# MAX30105.net
KiCad netlist of a schematic drawn in Altium Designer
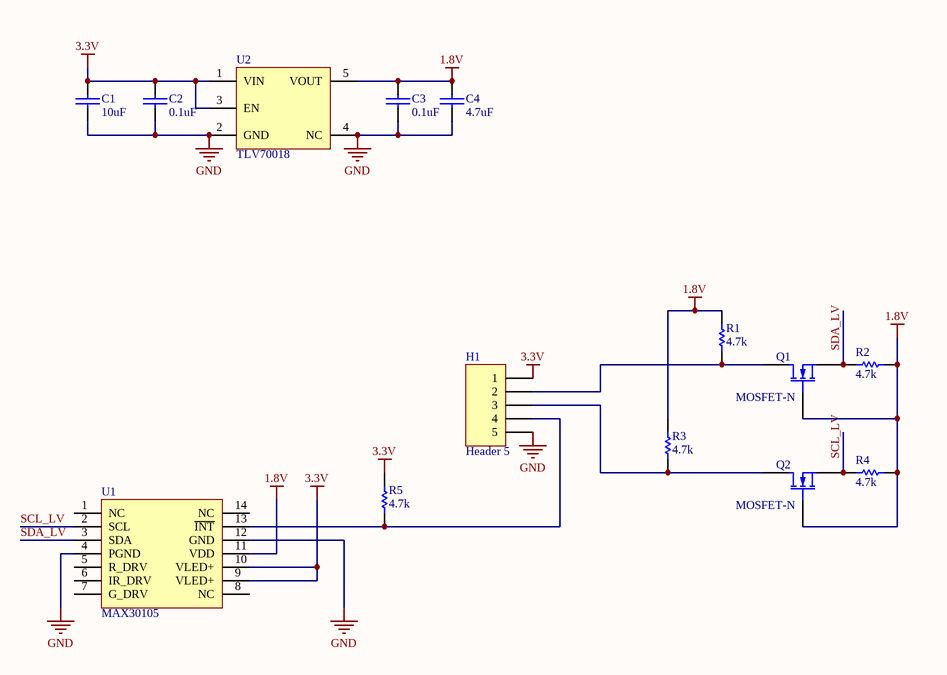
[diagram p0: MAX30105.SchDoc]

(export (version "E")
  (design (tool "Eeschema 10.0.6"))
  (components
    (comp (ref "C1")
      (value "10uF")
      (footprint "0402[IMP]")
      (fields (field (name "VOLTAGE") "CMAX"))
      (libsource (lib "Biosense_Altium_Library") (part "CAPACITOR"))
    )
    (comp (ref "C2")
      (value "0.1uF")
      (footprint "0402[IMP]")
      (fields (field (name "VOLTAGE") "CMAX"))
      (libsource (lib "Biosense_Altium_Library") (part "CAPACITOR"))
    )
    (comp (ref "C3")
      (value "0.1uF")
      (footprint "0402[IMP]")
      (fields (field (name "VOLTAGE") "CMAX"))
      (libsource (lib "Biosense_Altium_Library") (part "CAPACITOR"))
    )
    (comp (ref "C4")
      (value "4.7uF")
      (footprint "0402[IMP]")
      (fields (field (name "VOLTAGE") "CMAX"))
      (libsource (lib "Biosense_Altium_Library") (part "CAPACITOR"))
    )
    (comp (ref "H1")
      (value "Header 5")
      (footprint "I2C_Header")
      (libsource (lib "Biosense_Altium_Library") (part "Header 5"))
    )
    (comp (ref "Q1")
      (value "MOSFET-N")
      (footprint "SOT23")
      (description "N-Channel MOSFET")
      (fields (field (name "PUBLISHER") "Altium Limited"))
      (libsource (lib "Miscellaneous Devices") (part "MOSFET-N"))
    )
    (comp (ref "Q2")
      (value "MOSFET-N")
      (footprint "SOT23")
      (description "N-Channel MOSFET")
      (fields (field (name "PUBLISHER") "Altium Limited"))
      (libsource (lib "Miscellaneous Devices") (part "MOSFET-N"))
    )
    (comp (ref "R1")
      (value "4.7k")
      (footprint "0402[IMP]")
      (libsource (lib "Biosense_Altium_Library") (part "RESISTOR"))
    )
    (comp (ref "R2")
      (value "4.7k")
      (footprint "0402[IMP]")
      (libsource (lib "Biosense_Altium_Library") (part "RESISTOR"))
    )
    (comp (ref "R3")
      (value "4.7k")
      (footprint "0402[IMP]")
      (libsource (lib "Biosense_Altium_Library") (part "RESISTOR"))
    )
    (comp (ref "R4")
      (value "4.7k")
      (footprint "0402[IMP]")
      (libsource (lib "Biosense_Altium_Library") (part "RESISTOR"))
    )
    (comp (ref "R5")
      (value "4.7k")
      (footprint "0402[IMP]")
      (libsource (lib "Biosense_Altium_Library") (part "RESISTOR"))
    )
    (comp (ref "U1")
      (value "MAX30105")
      (footprint "OLGA-14")
      (libsource (lib "Biosense_Altium_Library") (part "MAX30105"))
    )
    (comp (ref "U2")
      (value "TLV70018")
      (footprint "SC70-5pin")
      (libsource (lib "Biosense_Altium_Library") (part "SP6214"))
    )
  )
  (nets
    (net (code "1") (name "/SCL_LV") (class "Default")
      (node (ref "Q2") (pin "3") (pinfunction "S_3") (pintype "passive"))
      (node (ref "R4") (pin "2") (pinfunction "2_2") (pintype "passive"))
      (node (ref "U1") (pin "2") (pinfunction "SCL_2") (pintype "passive"))
    )
    (net (code "2") (name "/SDA_LV") (class "Default")
      (node (ref "Q1") (pin "3") (pinfunction "S_3") (pintype "passive"))
      (node (ref "R2") (pin "2") (pinfunction "2_2") (pintype "passive"))
      (node (ref "U1") (pin "3") (pinfunction "SDA_3") (pintype "passive"))
    )
    (net (code "3") (name "1.8V") (class "Default")
      (node (ref "C3") (pin "1") (pinfunction "1_1") (pintype "passive"))
      (node (ref "C4") (pin "1") (pinfunction "1_1") (pintype "passive"))
      (node (ref "Q1") (pin "2") (pinfunction "G_2") (pintype "passive"))
      (node (ref "Q2") (pin "2") (pinfunction "G_2") (pintype "passive"))
      (node (ref "R1") (pin "2") (pinfunction "2_2") (pintype "passive"))
      (node (ref "R2") (pin "1") (pinfunction "1_1") (pintype "passive"))
      (node (ref "R3") (pin "2") (pinfunction "2_2") (pintype "passive"))
      (node (ref "R4") (pin "1") (pinfunction "1_1") (pintype "passive"))
      (node (ref "U1") (pin "11") (pinfunction "VDD_11") (pintype "passive"))
      (node (ref "U2") (pin "5") (pinfunction "VOUT_5") (pintype "passive"))
    )
    (net (code "4") (name "3.3V") (class "Default")
      (node (ref "C1") (pin "1") (pinfunction "1_1") (pintype "passive"))
      (node (ref "C2") (pin "1") (pinfunction "1_1") (pintype "passive"))
      (node (ref "H1") (pin "1") (pinfunction "1_1") (pintype "passive"))
      (node (ref "R5") (pin "2") (pinfunction "2_2") (pintype "passive"))
      (node (ref "U1") (pin "10") (pinfunction "VLED+_10") (pintype "passive"))
      (node (ref "U1") (pin "9") (pinfunction "VLED+_9") (pintype "passive"))
      (node (ref "U2") (pin "1") (pinfunction "VIN_1") (pintype "passive"))
      (node (ref "U2") (pin "3") (pinfunction "EN_3") (pintype "passive"))
    )
    (net (code "5") (name "GND") (class "Default")
      (node (ref "C1") (pin "2") (pinfunction "2_2") (pintype "passive"))
      (node (ref "C2") (pin "2") (pinfunction "2_2") (pintype "passive"))
      (node (ref "C3") (pin "2") (pinfunction "2_2") (pintype "passive"))
      (node (ref "C4") (pin "2") (pinfunction "2_2") (pintype "passive"))
      (node (ref "H1") (pin "5") (pinfunction "5_5") (pintype "passive"))
      (node (ref "U1") (pin "12") (pinfunction "GND_12") (pintype "passive"))
      (node (ref "U1") (pin "4") (pinfunction "PGND_4") (pintype "passive"))
      (node (ref "U2") (pin "2") (pinfunction "GND_2") (pintype "passive"))
      (node (ref "U2") (pin "4") (pinfunction "NC_4") (pintype "passive"))
    )
    (net (code "6") (name "Net-(Q1-D)") (class "Default")
      (node (ref "H1") (pin "2") (pinfunction "2_2") (pintype "passive"))
      (node (ref "Q1") (pin "1") (pinfunction "D_1") (pintype "passive"))
      (node (ref "R1") (pin "1") (pinfunction "1_1") (pintype "passive"))
    )
    (net (code "7") (name "Net-(Q2-D)") (class "Default")
      (node (ref "H1") (pin "3") (pinfunction "3_3") (pintype "passive"))
      (node (ref "Q2") (pin "1") (pinfunction "D_1") (pintype "passive"))
      (node (ref "R3") (pin "1") (pinfunction "1_1") (pintype "passive"))
    )
    (net (code "8") (name "Net-(U1-~{INT})") (class "Default")
      (node (ref "H1") (pin "4") (pinfunction "4_4") (pintype "passive"))
      (node (ref "R5") (pin "1") (pinfunction "1_1") (pintype "passive"))
      (node (ref "U1") (pin "13") (pinfunction "~{INT}_13") (pintype "passive"))
    )
    (net (code "9") (name "unconnected-(U1-G_DRV-Pad7)") (class "Default")
      (node (ref "U1") (pin "7") (pinfunction "G_DRV_7") (pintype "passive"))
    )
    (net (code "10") (name "unconnected-(U1-IR_DRV-Pad6)") (class "Default")
      (node (ref "U1") (pin "6") (pinfunction "IR_DRV_6") (pintype "passive"))
    )
    (net (code "11") (name "unconnected-(U1-NC-Pad1)") (class "Default")
      (node (ref "U1") (pin "1") (pinfunction "NC_1") (pintype "passive"))
    )
    (net (code "12") (name "unconnected-(U1-NC-Pad8)") (class "Default")
      (node (ref "U1") (pin "8") (pinfunction "NC_8") (pintype "passive"))
    )
    (net (code "13") (name "unconnected-(U1-NC-Pad14)") (class "Default")
      (node (ref "U1") (pin "14") (pinfunction "NC_14") (pintype "passive"))
    )
    (net (code "14") (name "unconnected-(U1-R_DRV-Pad5)") (class "Default")
      (node (ref "U1") (pin "5") (pinfunction "R_DRV_5") (pintype "passive"))
    )
  )
)
